# nanoController.net
KiCad netlist of a schematic drawn in EAGLE
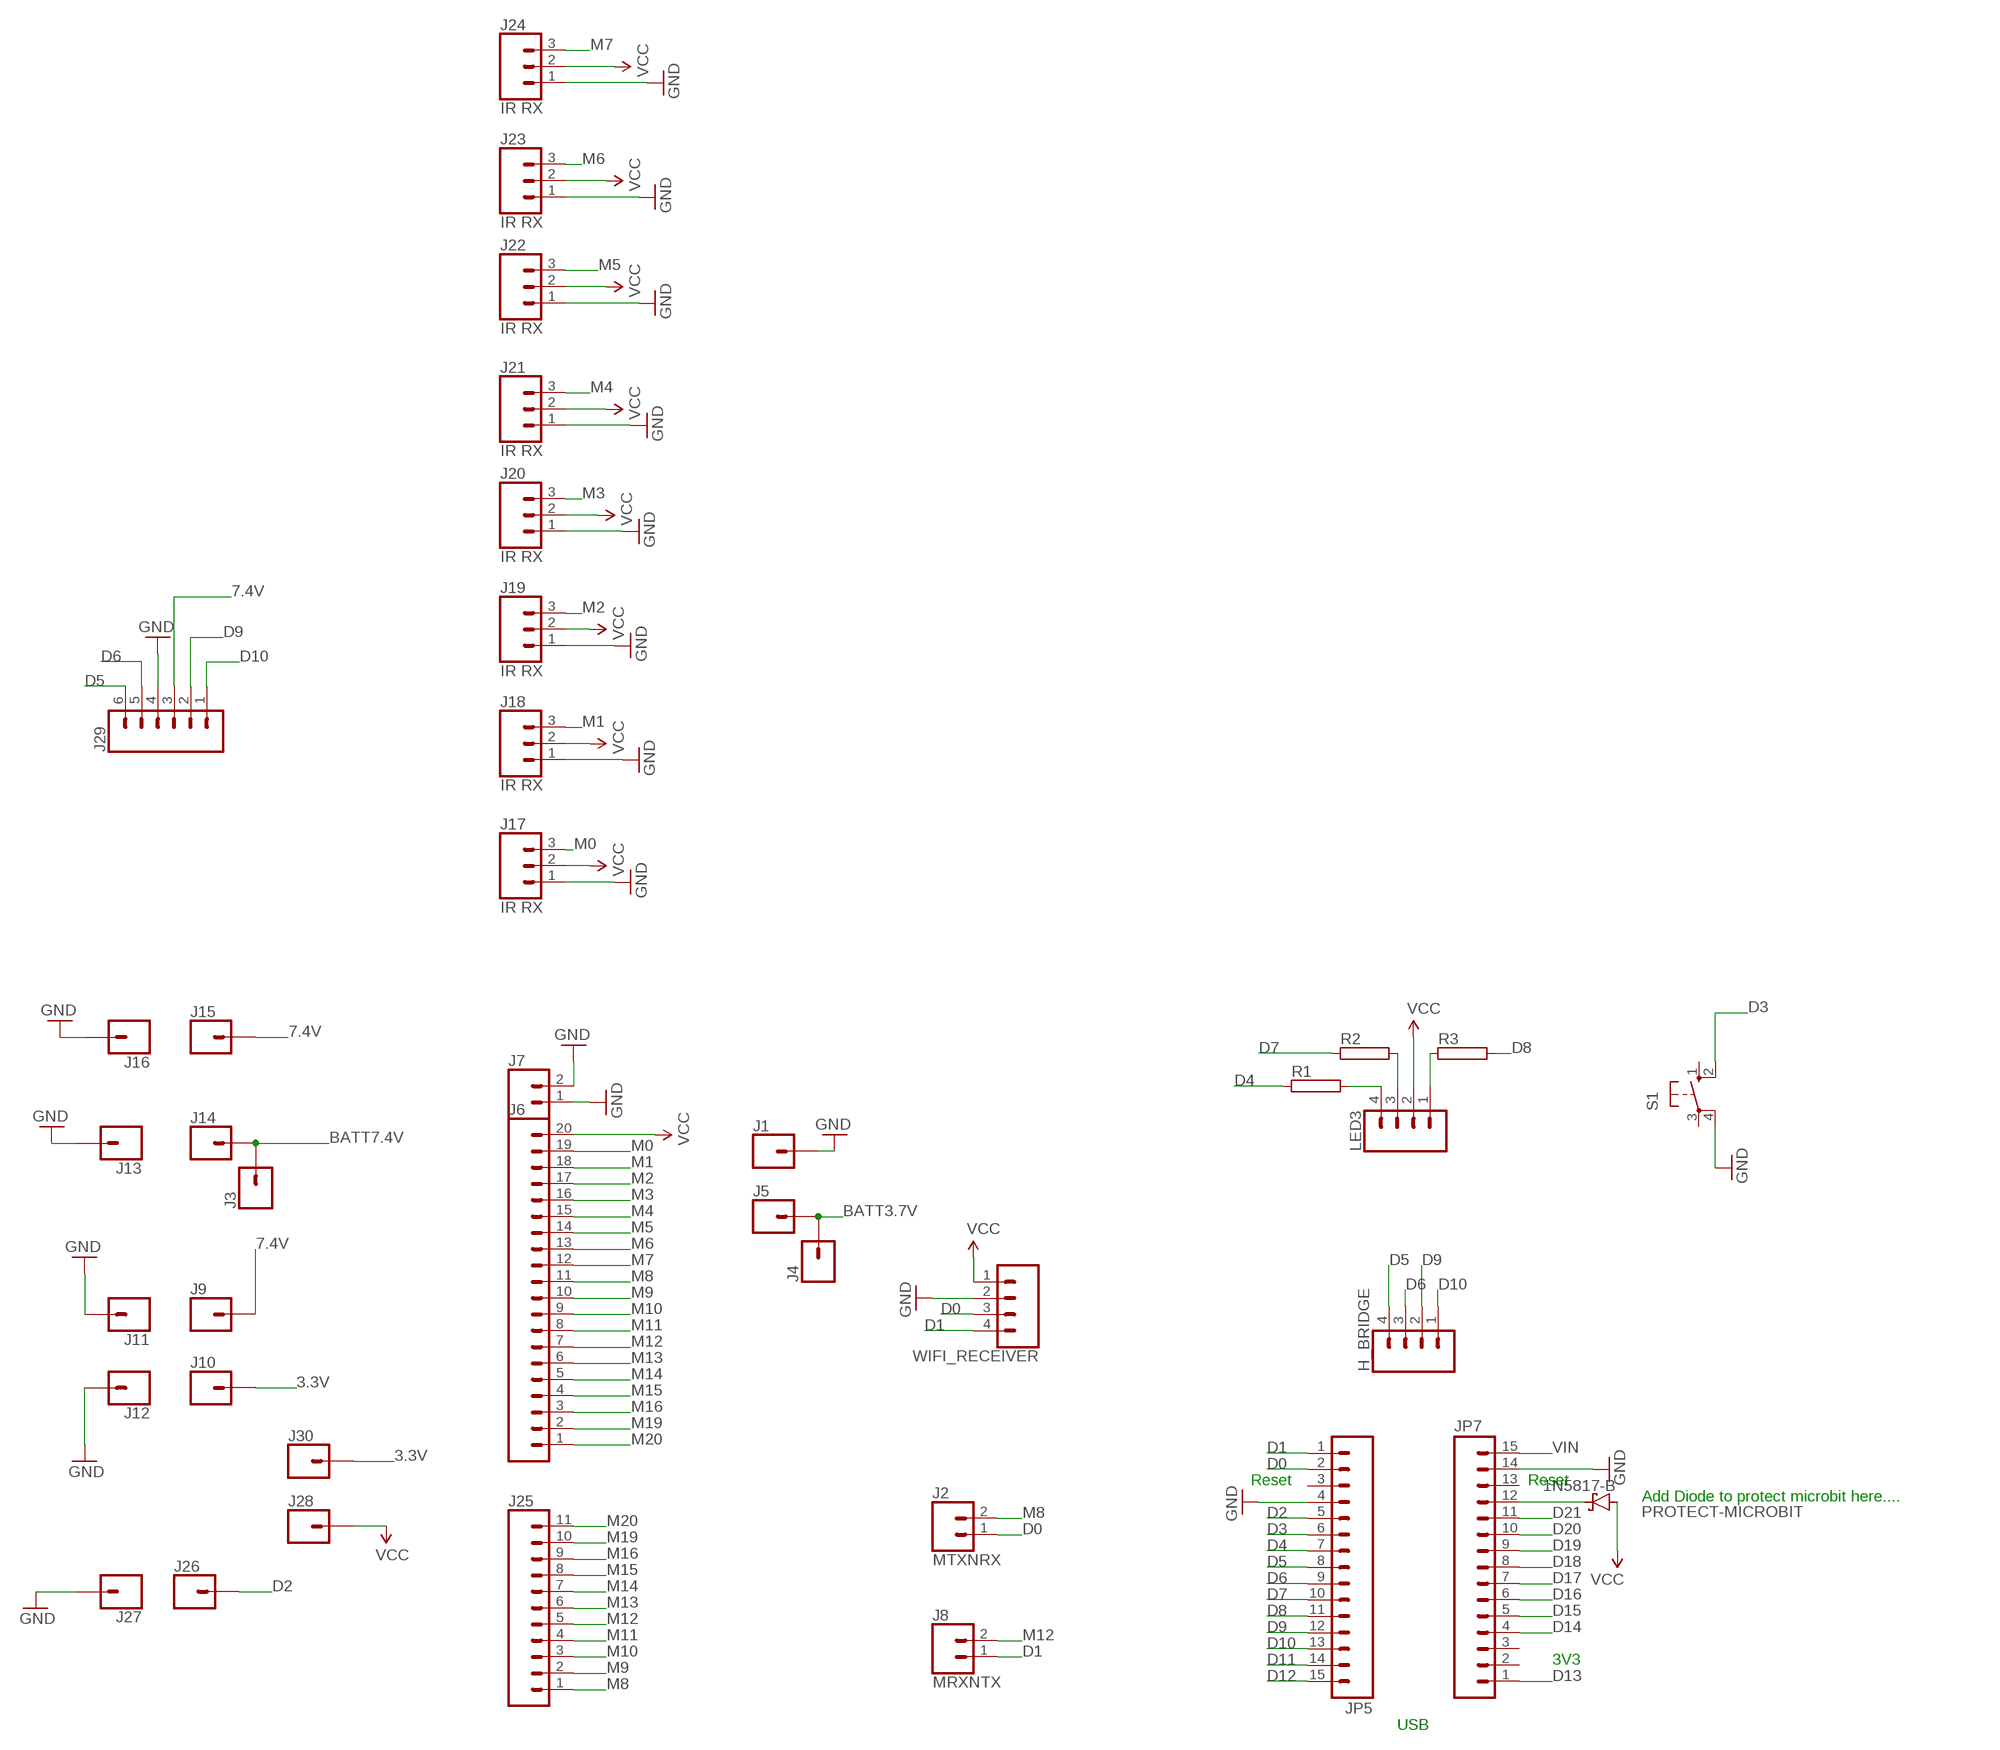
[diagram p0: schematic, sheet 1]

(export (version "E")
  (design (tool "Eeschema 10.0.6"))
  (components
    (comp (ref "H_BRIDGE")
      (value "CONN_04LONGPADS")
      (footprint "eagle-import:1X04_LONGPADS")
      (libsource (lib "eagle-import") (part "CONN_04LONGPADS"))
    )
    (comp (ref "J1")
      (value "CONN_01SMTSO-256-ET-0.165DIA")
      (footprint "eagle-import:SMTSO-256-ET-0.165DIA")
      (libsource (lib "eagle-import") (part "CONN_01SMTSO-256-ET-0.165DIA"))
    )
    (comp (ref "J2")
      (value "MTXNRX")
      (footprint "eagle-import:1X02")
      (libsource (lib "eagle-import") (part "CONN_02"))
    )
    (comp (ref "J3")
      (value "CONN_01")
      (footprint "eagle-import:1X01")
      (libsource (lib "eagle-import") (part "CONN_01"))
    )
    (comp (ref "J4")
      (value "CONN_01")
      (footprint "eagle-import:1X01")
      (libsource (lib "eagle-import") (part "CONN_01"))
    )
    (comp (ref "J5")
      (value "CONN_01SMTSO-256-ET-0.165DIA")
      (footprint "eagle-import:SMTSO-256-ET-0.165DIA")
      (libsource (lib "eagle-import") (part "CONN_01SMTSO-256-ET-0.165DIA"))
    )
    (comp (ref "J6")
      (value "CONN_20")
      (footprint "eagle-import:1X20")
      (libsource (lib "eagle-import") (part "CONN_20"))
    )
    (comp (ref "J7")
      (value "CONN_02")
      (footprint "eagle-import:1X02")
      (libsource (lib "eagle-import") (part "CONN_02"))
    )
    (comp (ref "J8")
      (value "MRXNTX")
      (footprint "eagle-import:1X02")
      (libsource (lib "eagle-import") (part "CONN_02"))
    )
    (comp (ref "J9")
      (value "CONN_01")
      (footprint "eagle-import:1X01")
      (libsource (lib "eagle-import") (part "CONN_01"))
    )
    (comp (ref "J10")
      (value "CONN_01")
      (footprint "eagle-import:1X01")
      (libsource (lib "eagle-import") (part "CONN_01"))
    )
    (comp (ref "J11")
      (value "CONN_01")
      (footprint "eagle-import:1X01")
      (libsource (lib "eagle-import") (part "CONN_01"))
    )
    (comp (ref "J12")
      (value "CONN_01")
      (footprint "eagle-import:1X01")
      (libsource (lib "eagle-import") (part "CONN_01"))
    )
    (comp (ref "J13")
      (value "CONN_01")
      (footprint "eagle-import:1X01")
      (libsource (lib "eagle-import") (part "CONN_01"))
    )
    (comp (ref "J14")
      (value "CONN_01")
      (footprint "eagle-import:1X01")
      (libsource (lib "eagle-import") (part "CONN_01"))
    )
    (comp (ref "J15")
      (value "CONN_01")
      (footprint "eagle-import:1X01")
      (libsource (lib "eagle-import") (part "CONN_01"))
    )
    (comp (ref "J16")
      (value "CONN_01")
      (footprint "eagle-import:1X01")
      (libsource (lib "eagle-import") (part "CONN_01"))
    )
    (comp (ref "J17")
      (value "IR RX")
      (footprint "eagle-import:1X03")
      (libsource (lib "eagle-import") (part "CONN_03"))
    )
    (comp (ref "J18")
      (value "IR RX")
      (footprint "eagle-import:1X03")
      (libsource (lib "eagle-import") (part "CONN_03"))
    )
    (comp (ref "J19")
      (value "IR RX")
      (footprint "eagle-import:1X03")
      (libsource (lib "eagle-import") (part "CONN_03"))
    )
    (comp (ref "J20")
      (value "IR RX")
      (footprint "eagle-import:1X03")
      (libsource (lib "eagle-import") (part "CONN_03"))
    )
    (comp (ref "J21")
      (value "IR RX")
      (footprint "eagle-import:1X03")
      (libsource (lib "eagle-import") (part "CONN_03"))
    )
    (comp (ref "J22")
      (value "IR RX")
      (footprint "eagle-import:1X03")
      (libsource (lib "eagle-import") (part "CONN_03"))
    )
    (comp (ref "J23")
      (value "IR RX")
      (footprint "eagle-import:1X03")
      (libsource (lib "eagle-import") (part "CONN_03"))
    )
    (comp (ref "J24")
      (value "IR RX")
      (footprint "eagle-import:1X03")
      (libsource (lib "eagle-import") (part "CONN_03"))
    )
    (comp (ref "J25")
      (value "CONN_11")
      (footprint "eagle-import:1X11")
      (libsource (lib "eagle-import") (part "CONN_11"))
    )
    (comp (ref "J26")
      (value "CONN_01")
      (footprint "eagle-import:1X01")
      (libsource (lib "eagle-import") (part "CONN_01"))
    )
    (comp (ref "J27")
      (value "CONN_01")
      (footprint "eagle-import:1X01")
      (libsource (lib "eagle-import") (part "CONN_01"))
    )
    (comp (ref "J28")
      (value "CONN_01")
      (footprint "eagle-import:1X01")
      (libsource (lib "eagle-import") (part "CONN_01"))
    )
    (comp (ref "J29")
      (value "CONN_06SILK_FEMALE_PTH")
      (footprint "eagle-import:1X06")
      (libsource (lib "eagle-import") (part "CONN_06SILK_FEMALE_PTH"))
    )
    (comp (ref "J30")
      (value "CONN_01")
      (footprint "eagle-import:1X01")
      (libsource (lib "eagle-import") (part "CONN_01"))
    )
    (comp (ref "JP5")
      (value "M15")
      (footprint "eagle-import:1X15")
      (libsource (lib "eagle-import") (part "M15"))
    )
    (comp (ref "JP7")
      (value "M15")
      (footprint "eagle-import:1X15")
      (libsource (lib "eagle-import") (part "M15"))
    )
    (comp (ref "LED3")
      (value "CONN_04LONGPADS")
      (footprint "eagle-import:1X04_LONGPADS")
      (libsource (lib "eagle-import") (part "CONN_04LONGPADS"))
    )
    (comp (ref "PROTECT-MICROBIT")
      (value "1N5817-B")
      (footprint "eagle-import:DO41-7.6")
      (libsource (lib "eagle-import") (part "1N5817-B"))
    )
    (comp (ref "R1")
      (value "RHPS58")
      (footprint "eagle-import:HPS58")
      (libsource (lib "eagle-import") (part "RHPS58"))
    )
    (comp (ref "R2")
      (value "RHPS58")
      (footprint "eagle-import:HPS58")
      (libsource (lib "eagle-import") (part "RHPS58"))
    )
    (comp (ref "R3")
      (value "RHPS58")
      (footprint "eagle-import:HPS58")
      (libsource (lib "eagle-import") (part "RHPS58"))
    )
    (comp (ref "S1")
      (value "10-XX")
      (footprint "eagle-import:B3F-10XX")
      (fields (field (name "MPN") "B3F-1000"))
      (libsource (lib "eagle-import") (part "10-XX"))
    )
    (comp (ref "WIFI_RECEIVER")
      (value "CONN_04LONGPADS")
      (footprint "eagle-import:1X04_LONGPADS")
      (libsource (lib "eagle-import") (part "CONN_04LONGPADS"))
    )
  )
  (nets
    (net (code "1") (name "/3.3V") (class "Default")
      (node (ref "J10") (pin "1") (pinfunction "1_1") (pintype "passive"))
      (node (ref "J30") (pin "1") (pinfunction "1_1") (pintype "passive"))
    )
    (net (code "2") (name "/7.4V") (class "Default")
      (node (ref "J15") (pin "1") (pinfunction "1_1") (pintype "passive"))
      (node (ref "J29") (pin "3") (pinfunction "3_3") (pintype "passive"))
      (node (ref "J9") (pin "1") (pinfunction "1_1") (pintype "passive"))
    )
    (net (code "3") (name "/BATT3.7V") (class "Default")
      (node (ref "J4") (pin "1") (pinfunction "1_1") (pintype "passive"))
      (node (ref "J5") (pin "P$1") (pinfunction "1_P$1") (pintype "passive"))
    )
    (net (code "4") (name "/BATT7.4V") (class "Default")
      (node (ref "J14") (pin "1") (pinfunction "1_1") (pintype "passive"))
      (node (ref "J3") (pin "1") (pinfunction "1_1") (pintype "passive"))
    )
    (net (code "5") (name "/D0") (class "Default")
      (node (ref "J2") (pin "1") (pinfunction "1_1") (pintype "passive"))
      (node (ref "JP5") (pin "2") (pinfunction "2_2") (pintype "passive"))
      (node (ref "WIFI_RECEIVER") (pin "3") (pinfunction "3_3") (pintype "passive"))
    )
    (net (code "6") (name "/D1") (class "Default")
      (node (ref "J8") (pin "1") (pinfunction "1_1") (pintype "passive"))
      (node (ref "JP5") (pin "1") (pinfunction "1_1") (pintype "passive"))
      (node (ref "WIFI_RECEIVER") (pin "4") (pinfunction "4_4") (pintype "passive"))
    )
    (net (code "7") (name "/D2") (class "Default")
      (node (ref "J26") (pin "1") (pinfunction "1_1") (pintype "passive"))
      (node (ref "JP5") (pin "5") (pinfunction "5_5") (pintype "passive"))
    )
    (net (code "8") (name "/D3") (class "Default")
      (node (ref "JP5") (pin "6") (pinfunction "6_6") (pintype "passive"))
      (node (ref "S1") (pin "2") (pinfunction "S1_2") (pintype "passive"))
    )
    (net (code "9") (name "/D4") (class "Default")
      (node (ref "JP5") (pin "7") (pinfunction "7_7") (pintype "passive"))
      (node (ref "R1") (pin "1") (pinfunction "1_1") (pintype "passive"))
    )
    (net (code "10") (name "/D5") (class "Default")
      (node (ref "H_BRIDGE") (pin "4") (pinfunction "4_4") (pintype "passive"))
      (node (ref "J29") (pin "6") (pinfunction "6_6") (pintype "passive"))
      (node (ref "JP5") (pin "8") (pinfunction "8_8") (pintype "passive"))
    )
    (net (code "11") (name "/D6") (class "Default")
      (node (ref "H_BRIDGE") (pin "3") (pinfunction "3_3") (pintype "passive"))
      (node (ref "J29") (pin "5") (pinfunction "5_5") (pintype "passive"))
      (node (ref "JP5") (pin "9") (pinfunction "9_9") (pintype "passive"))
    )
    (net (code "12") (name "/D7") (class "Default")
      (node (ref "JP5") (pin "10") (pinfunction "10_10") (pintype "passive"))
      (node (ref "R2") (pin "1") (pinfunction "1_1") (pintype "passive"))
    )
    (net (code "13") (name "/D8") (class "Default")
      (node (ref "JP5") (pin "11") (pinfunction "11_11") (pintype "passive"))
      (node (ref "R3") (pin "2") (pinfunction "2_2") (pintype "passive"))
    )
    (net (code "14") (name "/D9") (class "Default")
      (node (ref "H_BRIDGE") (pin "2") (pinfunction "2_2") (pintype "passive"))
      (node (ref "J29") (pin "2") (pinfunction "2_2") (pintype "passive"))
      (node (ref "JP5") (pin "12") (pinfunction "12_12") (pintype "passive"))
    )
    (net (code "15") (name "/D10") (class "Default")
      (node (ref "H_BRIDGE") (pin "1") (pinfunction "1_1") (pintype "passive"))
      (node (ref "J29") (pin "1") (pinfunction "1_1") (pintype "passive"))
      (node (ref "JP5") (pin "13") (pinfunction "13_13") (pintype "passive"))
    )
    (net (code "16") (name "/D11") (class "Default")
      (node (ref "JP5") (pin "14") (pinfunction "14_14") (pintype "passive"))
    )
    (net (code "17") (name "/D12") (class "Default")
      (node (ref "JP5") (pin "15") (pinfunction "15_15") (pintype "passive"))
    )
    (net (code "18") (name "/D13") (class "Default")
      (node (ref "JP7") (pin "1") (pinfunction "1_1") (pintype "passive"))
    )
    (net (code "19") (name "/D14") (class "Default")
      (node (ref "JP7") (pin "4") (pinfunction "4_4") (pintype "passive"))
    )
    (net (code "20") (name "/D15") (class "Default")
      (node (ref "JP7") (pin "5") (pinfunction "5_5") (pintype "passive"))
    )
    (net (code "21") (name "/D16") (class "Default")
      (node (ref "JP7") (pin "6") (pinfunction "6_6") (pintype "passive"))
    )
    (net (code "22") (name "/D17") (class "Default")
      (node (ref "JP7") (pin "7") (pinfunction "7_7") (pintype "passive"))
    )
    (net (code "23") (name "/D18") (class "Default")
      (node (ref "JP7") (pin "8") (pinfunction "8_8") (pintype "passive"))
    )
    (net (code "24") (name "/D19") (class "Default")
      (node (ref "JP7") (pin "9") (pinfunction "9_9") (pintype "passive"))
    )
    (net (code "25") (name "/D20") (class "Default")
      (node (ref "JP7") (pin "10") (pinfunction "10_10") (pintype "passive"))
    )
    (net (code "26") (name "/D21") (class "Default")
      (node (ref "JP7") (pin "11") (pinfunction "11_11") (pintype "passive"))
    )
    (net (code "27") (name "/M0") (class "Default")
      (node (ref "J17") (pin "3") (pinfunction "3_3") (pintype "passive"))
      (node (ref "J6") (pin "19") (pinfunction "19_19") (pintype "passive"))
    )
    (net (code "28") (name "/M1") (class "Default")
      (node (ref "J18") (pin "3") (pinfunction "3_3") (pintype "passive"))
      (node (ref "J6") (pin "18") (pinfunction "18_18") (pintype "passive"))
    )
    (net (code "29") (name "/M2") (class "Default")
      (node (ref "J19") (pin "3") (pinfunction "3_3") (pintype "passive"))
      (node (ref "J6") (pin "17") (pinfunction "17_17") (pintype "passive"))
    )
    (net (code "30") (name "/M3") (class "Default")
      (node (ref "J20") (pin "3") (pinfunction "3_3") (pintype "passive"))
      (node (ref "J6") (pin "16") (pinfunction "16_16") (pintype "passive"))
    )
    (net (code "31") (name "/M4") (class "Default")
      (node (ref "J21") (pin "3") (pinfunction "3_3") (pintype "passive"))
      (node (ref "J6") (pin "15") (pinfunction "15_15") (pintype "passive"))
    )
    (net (code "32") (name "/M5") (class "Default")
      (node (ref "J22") (pin "3") (pinfunction "3_3") (pintype "passive"))
      (node (ref "J6") (pin "14") (pinfunction "14_14") (pintype "passive"))
    )
    (net (code "33") (name "/M6") (class "Default")
      (node (ref "J23") (pin "3") (pinfunction "3_3") (pintype "passive"))
      (node (ref "J6") (pin "13") (pinfunction "13_13") (pintype "passive"))
    )
    (net (code "34") (name "/M7") (class "Default")
      (node (ref "J24") (pin "3") (pinfunction "3_3") (pintype "passive"))
      (node (ref "J6") (pin "12") (pinfunction "12_12") (pintype "passive"))
    )
    (net (code "35") (name "/M8") (class "Default")
      (node (ref "J2") (pin "2") (pinfunction "2_2") (pintype "passive"))
      (node (ref "J25") (pin "1") (pinfunction "1_1") (pintype "passive"))
      (node (ref "J6") (pin "11") (pinfunction "11_11") (pintype "passive"))
    )
    (net (code "36") (name "/M9") (class "Default")
      (node (ref "J25") (pin "2") (pinfunction "2_2") (pintype "passive"))
      (node (ref "J6") (pin "10") (pinfunction "10_10") (pintype "passive"))
    )
    (net (code "37") (name "/M10") (class "Default")
      (node (ref "J25") (pin "3") (pinfunction "3_3") (pintype "passive"))
      (node (ref "J6") (pin "9") (pinfunction "9_9") (pintype "passive"))
    )
    (net (code "38") (name "/M11") (class "Default")
      (node (ref "J25") (pin "4") (pinfunction "4_4") (pintype "passive"))
      (node (ref "J6") (pin "8") (pinfunction "8_8") (pintype "passive"))
    )
    (net (code "39") (name "/M12") (class "Default")
      (node (ref "J25") (pin "5") (pinfunction "5_5") (pintype "passive"))
      (node (ref "J6") (pin "7") (pinfunction "7_7") (pintype "passive"))
      (node (ref "J8") (pin "2") (pinfunction "2_2") (pintype "passive"))
    )
    (net (code "40") (name "/M13") (class "Default")
      (node (ref "J25") (pin "6") (pinfunction "6_6") (pintype "passive"))
      (node (ref "J6") (pin "6") (pinfunction "6_6") (pintype "passive"))
    )
    (net (code "41") (name "/M14") (class "Default")
      (node (ref "J25") (pin "7") (pinfunction "7_7") (pintype "passive"))
      (node (ref "J6") (pin "5") (pinfunction "5_5") (pintype "passive"))
    )
    (net (code "42") (name "/M15") (class "Default")
      (node (ref "J25") (pin "8") (pinfunction "8_8") (pintype "passive"))
      (node (ref "J6") (pin "4") (pinfunction "4_4") (pintype "passive"))
    )
    (net (code "43") (name "/M16") (class "Default")
      (node (ref "J25") (pin "9") (pinfunction "9_9") (pintype "passive"))
      (node (ref "J6") (pin "3") (pinfunction "3_3") (pintype "passive"))
    )
    (net (code "44") (name "/M19") (class "Default")
      (node (ref "J25") (pin "10") (pinfunction "10_10") (pintype "passive"))
      (node (ref "J6") (pin "2") (pinfunction "2_2") (pintype "passive"))
    )
    (net (code "45") (name "/M20") (class "Default")
      (node (ref "J25") (pin "11") (pinfunction "11_11") (pintype "passive"))
      (node (ref "J6") (pin "1") (pinfunction "1_1") (pintype "passive"))
    )
    (net (code "46") (name "/VIN") (class "Default")
      (node (ref "JP7") (pin "15") (pinfunction "15_15") (pintype "passive"))
    )
    (net (code "47") (name "GND") (class "Default")
      (node (ref "J1") (pin "P$1") (pinfunction "1_P$1") (pintype "passive"))
      (node (ref "J11") (pin "1") (pinfunction "1_1") (pintype "passive"))
      (node (ref "J12") (pin "1") (pinfunction "1_1") (pintype "passive"))
      (node (ref "J13") (pin "1") (pinfunction "1_1") (pintype "passive"))
      (node (ref "J16") (pin "1") (pinfunction "1_1") (pintype "passive"))
      (node (ref "J17") (pin "1") (pinfunction "1_1") (pintype "passive"))
      (node (ref "J18") (pin "1") (pinfunction "1_1") (pintype "passive"))
      (node (ref "J19") (pin "1") (pinfunction "1_1") (pintype "passive"))
      (node (ref "J20") (pin "1") (pinfunction "1_1") (pintype "passive"))
      (node (ref "J21") (pin "1") (pinfunction "1_1") (pintype "passive"))
      (node (ref "J22") (pin "1") (pinfunction "1_1") (pintype "passive"))
      (node (ref "J23") (pin "1") (pinfunction "1_1") (pintype "passive"))
      (node (ref "J24") (pin "1") (pinfunction "1_1") (pintype "passive"))
      (node (ref "J27") (pin "1") (pinfunction "1_1") (pintype "passive"))
      (node (ref "J29") (pin "4") (pinfunction "4_4") (pintype "passive"))
      (node (ref "J7") (pin "1") (pinfunction "1_1") (pintype "passive"))
      (node (ref "J7") (pin "2") (pinfunction "2_2") (pintype "passive"))
      (node (ref "JP5") (pin "4") (pinfunction "4_4") (pintype "passive"))
      (node (ref "JP7") (pin "14") (pinfunction "14_14") (pintype "passive"))
      (node (ref "S1") (pin "4") (pinfunction "P1_4") (pintype "passive"))
      (node (ref "WIFI_RECEIVER") (pin "2") (pinfunction "2_2") (pintype "passive"))
    )
    (net (code "48") (name "Net-(JP7-Pad12)") (class "Default")
      (node (ref "JP7") (pin "12") (pinfunction "12_12") (pintype "passive"))
      (node (ref "PROTECT-MICROBIT") (pin "C") (pinfunction "C_C") (pintype "passive"))
    )
    (net (code "49") (name "Net-(LED3-Pad1)") (class "Default")
      (node (ref "LED3") (pin "1") (pinfunction "1_1") (pintype "passive"))
      (node (ref "R3") (pin "1") (pinfunction "1_1") (pintype "passive"))
    )
    (net (code "50") (name "Net-(LED3-Pad3)") (class "Default")
      (node (ref "LED3") (pin "3") (pinfunction "3_3") (pintype "passive"))
      (node (ref "R2") (pin "2") (pinfunction "2_2") (pintype "passive"))
    )
    (net (code "51") (name "Net-(LED3-Pad4)") (class "Default")
      (node (ref "LED3") (pin "4") (pinfunction "4_4") (pintype "passive"))
      (node (ref "R1") (pin "2") (pinfunction "2_2") (pintype "passive"))
    )
    (net (code "52") (name "VCC") (class "Default")
      (node (ref "J17") (pin "2") (pinfunction "2_2") (pintype "passive"))
      (node (ref "J18") (pin "2") (pinfunction "2_2") (pintype "passive"))
      (node (ref "J19") (pin "2") (pinfunction "2_2") (pintype "passive"))
      (node (ref "J20") (pin "2") (pinfunction "2_2") (pintype "passive"))
      (node (ref "J21") (pin "2") (pinfunction "2_2") (pintype "passive"))
      (node (ref "J22") (pin "2") (pinfunction "2_2") (pintype "passive"))
      (node (ref "J23") (pin "2") (pinfunction "2_2") (pintype "passive"))
      (node (ref "J24") (pin "2") (pinfunction "2_2") (pintype "passive"))
      (node (ref "J28") (pin "1") (pinfunction "1_1") (pintype "passive"))
      (node (ref "J6") (pin "20") (pinfunction "20_20") (pintype "passive"))
      (node (ref "LED3") (pin "2") (pinfunction "2_2") (pintype "passive"))
      (node (ref "PROTECT-MICROBIT") (pin "A") (pinfunction "A_A") (pintype "passive"))
      (node (ref "WIFI_RECEIVER") (pin "1") (pinfunction "1_1") (pintype "passive"))
    )
    (net (code "53") (name "unconnected-(JP5-Pad3)") (class "Default")
      (node (ref "JP5") (pin "3") (pinfunction "3_3") (pintype "passive"))
    )
    (net (code "54") (name "unconnected-(JP7-Pad2)") (class "Default")
      (node (ref "JP7") (pin "2") (pinfunction "2_2") (pintype "passive"))
    )
    (net (code "55") (name "unconnected-(JP7-Pad3)") (class "Default")
      (node (ref "JP7") (pin "3") (pinfunction "3_3") (pintype "passive"))
    )
    (net (code "56") (name "unconnected-(JP7-Pad13)") (class "Default")
      (node (ref "JP7") (pin "13") (pinfunction "13_13") (pintype "passive"))
    )
    (net (code "57") (name "unconnected-(S1-P-Pad3)") (class "Default")
      (node (ref "S1") (pin "3") (pinfunction "P_3") (pintype "passive"))
    )
    (net (code "58") (name "unconnected-(S1-S-Pad1)") (class "Default")
      (node (ref "S1") (pin "1") (pinfunction "S_1") (pintype "passive"))
    )
  )
)
